# Mcu.net
KiCad netlist of a schematic drawn in Altium Designer
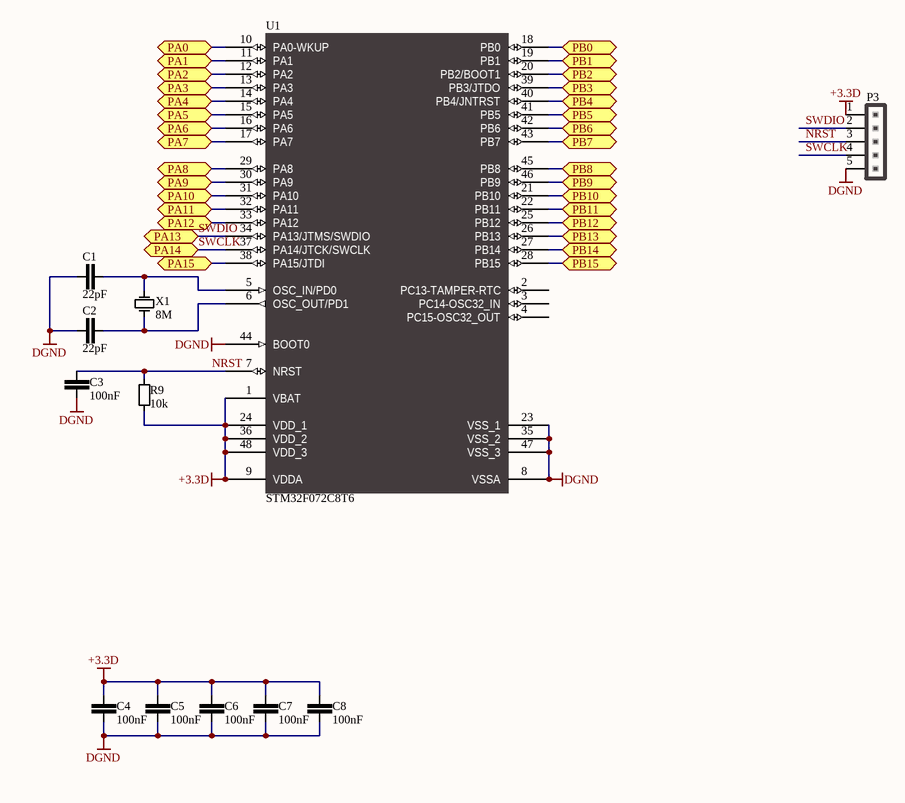
[diagram p0: Mcu.SchDoc]

(export (version "E")
  (design (tool "Eeschema 10.0.6"))
  (components
    (comp (ref "C1")
      (value "22pF")
      (footprint "GreenBox:0603-C")
      (description "MLCC 22pF 5% 50V NPO 0603")
      (fields (field (name "Comment") "Cap") (field (name "PUBLISHER") "GreenBox"))
      (libsource (lib "Capacitor") (part "C11C022PJ1H0"))
    )
    (comp (ref "C2")
      (value "22pF")
      (footprint "GreenBox:0603-C")
      (description "MLCC 22pF 5% 50V NPO 0603")
      (fields (field (name "Comment") "Cap") (field (name "PUBLISHER") "GreenBox"))
      (libsource (lib "Capacitor") (part "C11C022PJ1H0"))
    )
    (comp (ref "C3")
      (value "100nF")
      (footprint "GreenBox:0603-C")
      (description "MLCC 100nF 10% 50V X7R 0603")
      (fields (field (name "Comment") "Cap") (field (name "PUBLISHER") "GreenBox"))
      (libsource (lib "Capacitor") (part "C21C100NK1H0"))
    )
    (comp (ref "C4")
      (value "100nF")
      (footprint "GreenBox:0603-C")
      (description "MLCC 100nF 10% 50V X7R 0603")
      (fields (field (name "Comment") "Cap") (field (name "PUBLISHER") "GreenBox"))
      (libsource (lib "Capacitor") (part "C21C100NK1H0"))
    )
    (comp (ref "C5")
      (value "100nF")
      (footprint "GreenBox:0603-C")
      (description "MLCC 100nF 10% 50V X7R 0603")
      (fields (field (name "Comment") "Cap") (field (name "PUBLISHER") "GreenBox"))
      (libsource (lib "Capacitor") (part "C21C100NK1H0"))
    )
    (comp (ref "C6")
      (value "100nF")
      (footprint "GreenBox:0603-C")
      (description "MLCC 100nF 10% 50V X7R 0603")
      (fields (field (name "Comment") "Cap") (field (name "PUBLISHER") "GreenBox"))
      (libsource (lib "Capacitor") (part "C21C100NK1H0"))
    )
    (comp (ref "C7")
      (value "100nF")
      (footprint "GreenBox:0603-C")
      (description "MLCC 100nF 10% 50V X7R 0603")
      (fields (field (name "Comment") "Cap") (field (name "PUBLISHER") "GreenBox"))
      (libsource (lib "Capacitor") (part "C21C100NK1H0"))
    )
    (comp (ref "C8")
      (value "100nF")
      (footprint "GreenBox:0603-C")
      (description "MLCC 100nF 10% 50V X7R 0603")
      (fields (field (name "Comment") "Cap") (field (name "PUBLISHER") "GreenBox"))
      (libsource (lib "Capacitor") (part "C21C100NK1H0"))
    )
    (comp (ref "P3")
      (value "Header 5")
      (footprint "GreenBox:HDR-1X5")
      (description "Header 5-Pin Pitch 2.54mm Height 11mm")
      (fields (field (name "PUBLISHER") "GreenBox"))
      (libsource (lib "Connectors") (part "P1D105Z254D0"))
    )
    (comp (ref "R9")
      (value "10k")
      (footprint "GreenBox:0603-R")
      (description "SMD Resistor 10k 1% 1/10W 0603 100PPM")
      (fields (field (name "Comment") "Res") (field (name "PUBLISHER") "GreenBox"))
      (libsource (lib "Resistor") (part "R11C010KFBF0"))
    )
    (comp (ref "U1")
      (value "STM32F072C8T6")
      (footprint "GreenBox:LQFP48_N")
      (description "ARM CORTEXM3 STM32F072C8T6")
      (fields (field (name "MANUFACTURER") "ST") (field (name "PUBLISHER") "GreenBox"))
      (libsource (lib "Microcontroller") (part "UML3072C8T6S"))
    )
    (comp (ref "X1")
      (value "8M")
      (footprint "GreenBox:5032")
      (description "Crystal 8M 5032 50PPM")
      (fields
        (field (name "MANUFACTURER") "NDK")
        (field (name "Comment") "Crystal")
        (field (name "PUBLISHER") "GreenBox")
      )
      (libsource (lib "Crystal") (part "XC23000008M1"))
    )
  )
  (nets
    (net (code "1") (name "+3.3D") (class "Default")
      (node (ref "C4") (pin "1") (pinfunction "1_1") (pintype "passive"))
      (node (ref "C5") (pin "1") (pinfunction "1_1") (pintype "passive"))
      (node (ref "C6") (pin "1") (pinfunction "1_1") (pintype "passive"))
      (node (ref "C7") (pin "1") (pinfunction "1_1") (pintype "passive"))
      (node (ref "C8") (pin "1") (pinfunction "1_1") (pintype "passive"))
      (node (ref "P3") (pin "1") (pinfunction "1_1") (pintype "passive"))
      (node (ref "R9") (pin "2") (pinfunction "2_2") (pintype "passive"))
      (node (ref "U1") (pin "1") (pinfunction "VBAT_1") (pintype "power_in"))
      (node (ref "U1") (pin "24") (pinfunction "VDD_1_24") (pintype "power_in"))
      (node (ref "U1") (pin "36") (pinfunction "VDD_2_36") (pintype "power_in"))
      (node (ref "U1") (pin "48") (pinfunction "VDD_3_48") (pintype "power_in"))
      (node (ref "U1") (pin "9") (pinfunction "VDDA_9") (pintype "power_in"))
    )
    (net (code "2") (name "/NRST") (class "Default")
      (node (ref "C3") (pin "2") (pinfunction "2_2") (pintype "passive"))
      (node (ref "P3") (pin "3") (pinfunction "3_3") (pintype "passive"))
      (node (ref "R9") (pin "1") (pinfunction "1_1") (pintype "passive"))
      (node (ref "U1") (pin "7") (pinfunction "NRST_7") (pintype "bidirectional"))
    )
    (net (code "3") (name "/PA0") (class "Default")
      (node (ref "U1") (pin "10") (pinfunction "PA0-WKUP_10") (pintype "bidirectional"))
    )
    (net (code "4") (name "/PA1") (class "Default")
      (node (ref "U1") (pin "11") (pinfunction "PA1_11") (pintype "bidirectional"))
    )
    (net (code "5") (name "/PA2") (class "Default")
      (node (ref "U1") (pin "12") (pinfunction "PA2_12") (pintype "bidirectional"))
    )
    (net (code "6") (name "/PA3") (class "Default")
      (node (ref "U1") (pin "13") (pinfunction "PA3_13") (pintype "bidirectional"))
    )
    (net (code "7") (name "/PA4") (class "Default")
      (node (ref "U1") (pin "14") (pinfunction "PA4_14") (pintype "bidirectional"))
    )
    (net (code "8") (name "/PA5") (class "Default")
      (node (ref "U1") (pin "15") (pinfunction "PA5_15") (pintype "bidirectional"))
    )
    (net (code "9") (name "/PA6") (class "Default")
      (node (ref "U1") (pin "16") (pinfunction "PA6_16") (pintype "bidirectional"))
    )
    (net (code "10") (name "/PA7") (class "Default")
      (node (ref "U1") (pin "17") (pinfunction "PA7_17") (pintype "bidirectional"))
    )
    (net (code "11") (name "/PA8") (class "Default")
      (node (ref "U1") (pin "29") (pinfunction "PA8_29") (pintype "bidirectional"))
    )
    (net (code "12") (name "/PA9") (class "Default")
      (node (ref "U1") (pin "30") (pinfunction "PA9_30") (pintype "bidirectional"))
    )
    (net (code "13") (name "/PA10") (class "Default")
      (node (ref "U1") (pin "31") (pinfunction "PA10_31") (pintype "bidirectional"))
    )
    (net (code "14") (name "/PA11") (class "Default")
      (node (ref "U1") (pin "32") (pinfunction "PA11_32") (pintype "bidirectional"))
    )
    (net (code "15") (name "/PA12") (class "Default")
      (node (ref "U1") (pin "33") (pinfunction "PA12_33") (pintype "bidirectional"))
    )
    (net (code "16") (name "/PA15") (class "Default")
      (node (ref "U1") (pin "38") (pinfunction "PA15/JTDI_38") (pintype "bidirectional"))
    )
    (net (code "17") (name "/PB0") (class "Default")
      (node (ref "U1") (pin "18") (pinfunction "PB0_18") (pintype "bidirectional"))
    )
    (net (code "18") (name "/PB1") (class "Default")
      (node (ref "U1") (pin "19") (pinfunction "PB1_19") (pintype "bidirectional"))
    )
    (net (code "19") (name "/PB2") (class "Default")
      (node (ref "U1") (pin "20") (pinfunction "PB2/BOOT1_20") (pintype "bidirectional"))
    )
    (net (code "20") (name "/PB3") (class "Default")
      (node (ref "U1") (pin "39") (pinfunction "PB3/JTDO_39") (pintype "bidirectional"))
    )
    (net (code "21") (name "/PB4") (class "Default")
      (node (ref "U1") (pin "40") (pinfunction "PB4/JNTRST_40") (pintype "bidirectional"))
    )
    (net (code "22") (name "/PB5") (class "Default")
      (node (ref "U1") (pin "41") (pinfunction "PB5_41") (pintype "bidirectional"))
    )
    (net (code "23") (name "/PB6") (class "Default")
      (node (ref "U1") (pin "42") (pinfunction "PB6_42") (pintype "bidirectional"))
    )
    (net (code "24") (name "/PB7") (class "Default")
      (node (ref "U1") (pin "43") (pinfunction "PB7_43") (pintype "bidirectional"))
    )
    (net (code "25") (name "/PB8") (class "Default")
      (node (ref "U1") (pin "45") (pinfunction "PB8_45") (pintype "bidirectional"))
    )
    (net (code "26") (name "/PB9") (class "Default")
      (node (ref "U1") (pin "46") (pinfunction "PB9_46") (pintype "bidirectional"))
    )
    (net (code "27") (name "/PB10") (class "Default")
      (node (ref "U1") (pin "21") (pinfunction "PB10_21") (pintype "bidirectional"))
    )
    (net (code "28") (name "/PB11") (class "Default")
      (node (ref "U1") (pin "22") (pinfunction "PB11_22") (pintype "bidirectional"))
    )
    (net (code "29") (name "/PB12") (class "Default")
      (node (ref "U1") (pin "25") (pinfunction "PB12_25") (pintype "bidirectional"))
    )
    (net (code "30") (name "/PB13") (class "Default")
      (node (ref "U1") (pin "26") (pinfunction "PB13_26") (pintype "bidirectional"))
    )
    (net (code "31") (name "/PB14") (class "Default")
      (node (ref "U1") (pin "27") (pinfunction "PB14_27") (pintype "bidirectional"))
    )
    (net (code "32") (name "/PB15") (class "Default")
      (node (ref "U1") (pin "28") (pinfunction "PB15_28") (pintype "bidirectional"))
    )
    (net (code "33") (name "/SWCLK") (class "Default")
      (node (ref "P3") (pin "4") (pinfunction "4_4") (pintype "passive"))
      (node (ref "U1") (pin "37") (pinfunction "PA14/JTCK/SWCLK_37") (pintype "bidirectional"))
    )
    (net (code "34") (name "/SWDIO") (class "Default")
      (node (ref "P3") (pin "2") (pinfunction "2_2") (pintype "passive"))
      (node (ref "U1") (pin "34") (pinfunction "PA13/JTMS/SWDIO_34") (pintype "bidirectional"))
    )
    (net (code "35") (name "DGND") (class "Default")
      (node (ref "C1") (pin "1") (pinfunction "1_1") (pintype "passive"))
      (node (ref "C2") (pin "1") (pinfunction "1_1") (pintype "passive"))
      (node (ref "C3") (pin "1") (pinfunction "1_1") (pintype "passive"))
      (node (ref "C4") (pin "2") (pinfunction "2_2") (pintype "passive"))
      (node (ref "C5") (pin "2") (pinfunction "2_2") (pintype "passive"))
      (node (ref "C6") (pin "2") (pinfunction "2_2") (pintype "passive"))
      (node (ref "C7") (pin "2") (pinfunction "2_2") (pintype "passive"))
      (node (ref "C8") (pin "2") (pinfunction "2_2") (pintype "passive"))
      (node (ref "P3") (pin "5") (pinfunction "5_5") (pintype "passive"))
      (node (ref "U1") (pin "23") (pinfunction "VSS_1_23") (pintype "power_in"))
      (node (ref "U1") (pin "35") (pinfunction "VSS_2_35") (pintype "power_in"))
      (node (ref "U1") (pin "44") (pinfunction "BOOT0_44") (pintype "input"))
      (node (ref "U1") (pin "47") (pinfunction "VSS_3_47") (pintype "power_in"))
      (node (ref "U1") (pin "8") (pinfunction "VSSA_8") (pintype "power_in"))
    )
    (net (code "36") (name "Net-(U1-OSC_IN{slash}PD0)") (class "Default")
      (node (ref "C1") (pin "2") (pinfunction "2_2") (pintype "passive"))
      (node (ref "U1") (pin "5") (pinfunction "OSC_IN/PD0_5") (pintype "input"))
      (node (ref "X1") (pin "2") (pinfunction "OSC2_2") (pintype "passive"))
    )
    (net (code "37") (name "Net-(U1-OSC_OUT{slash}PD1)") (class "Default")
      (node (ref "C2") (pin "2") (pinfunction "2_2") (pintype "passive"))
      (node (ref "U1") (pin "6") (pinfunction "OSC_OUT/PD1_6") (pintype "output"))
      (node (ref "X1") (pin "1") (pinfunction "OSC1_1") (pintype "passive"))
    )
    (net (code "38") (name "unconnected-(U1-PC13-TAMPER-RTC-Pad2)") (class "Default")
      (node (ref "U1") (pin "2") (pinfunction "PC13-TAMPER-RTC_2") (pintype "bidirectional"))
    )
    (net (code "39") (name "unconnected-(U1-PC14-OSC32_IN-Pad3)") (class "Default")
      (node (ref "U1") (pin "3") (pinfunction "PC14-OSC32_IN_3") (pintype "bidirectional"))
    )
    (net (code "40") (name "unconnected-(U1-PC15-OSC32_OUT-Pad4)") (class "Default")
      (node (ref "U1") (pin "4") (pinfunction "PC15-OSC32_OUT_4") (pintype "bidirectional"))
    )
  )
)
